# telemetry-daughter.net
KiCad netlist of a schematic drawn in EAGLE
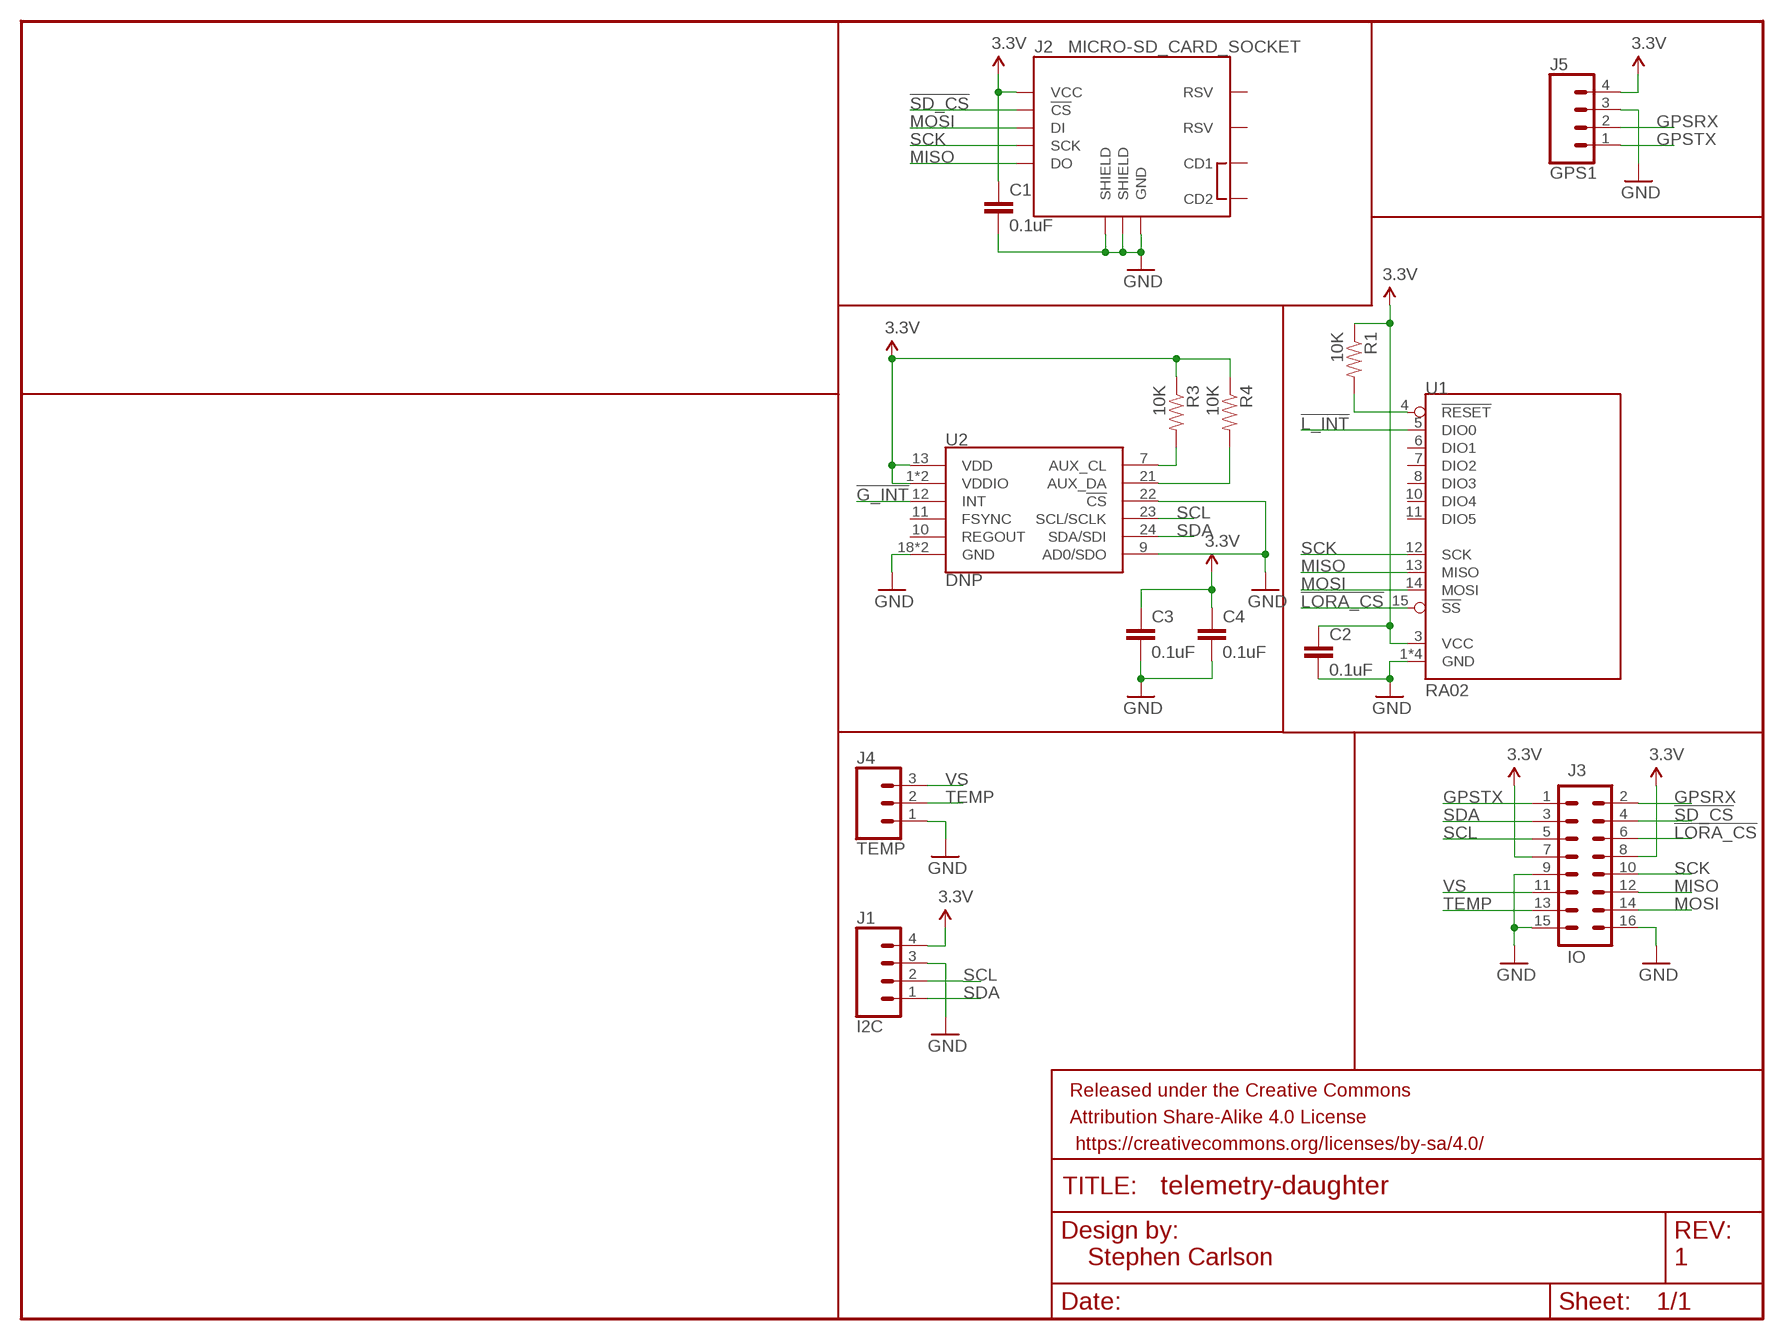
[diagram p0: schematic, sheet 1]

(export (version "E")
  (design (tool "Eeschema 10.0.6"))
  (components
    (comp (ref "C1")
      (value "0.1uF")
      (footprint "eagle-import:0603")
      (libsource (lib "eagle-import") (part "0.1UF-0603-25V-(+80/-20%)"))
    )
    (comp (ref "C2")
      (value "0.1uF")
      (footprint "eagle-import:0603")
      (libsource (lib "eagle-import") (part "0.1UF-0603-25V-(+80/-20%)"))
    )
    (comp (ref "C3")
      (value "0.1uF")
      (footprint "eagle-import:0603")
      (libsource (lib "eagle-import") (part "0.1UF-0603-25V-(+80/-20%)"))
    )
    (comp (ref "C4")
      (value "0.1uF")
      (footprint "eagle-import:0603")
      (libsource (lib "eagle-import") (part "0.1UF-0603-25V-(+80/-20%)"))
    )
    (comp (ref "FRAME1")
      (value "FRAME-LETTERNO_PACKAGE")
      (footprint "eagle-import:DUMMY")
      (fields (field (name "DESIGNER") "Nobody"))
      (libsource (lib "eagle-import") (part "FRAME-LETTERNO_PACKAGE"))
    )
    (comp (ref "J1")
      (value "I2C")
      (footprint "eagle-import:JST-4-PTH")
      (libsource (lib "eagle-import") (part "CONN_04JST-PTH"))
    )
    (comp (ref "J2")
      (value "MICRO-SD_CARD_SOCKET")
      (footprint "eagle-import:MICRO-SD-SOCKET")
      (libsource (lib "eagle-import") (part "MICRO-SD_CARD_SOCKET"))
    )
    (comp (ref "J3")
      (value "IO")
      (footprint "eagle-import:2X8")
      (libsource (lib "eagle-import") (part "M08X2"))
    )
    (comp (ref "J4")
      (value "TEMP")
      (footprint "eagle-import:JST-3-PTH")
      (libsource (lib "eagle-import") (part "CONN_03JST-PTH"))
    )
    (comp (ref "J5")
      (value "GPS1")
      (footprint "eagle-import:JST-4-PTH")
      (libsource (lib "eagle-import") (part "CONN_04JST-PTH"))
    )
    (comp (ref "R1")
      (value "10K")
      (footprint "eagle-import:0805")
      (libsource (lib "eagle-import") (part "RESISTOR0805-RES"))
    )
    (comp (ref "R3")
      (value "10K")
      (footprint "eagle-import:0805")
      (libsource (lib "eagle-import") (part "RESISTOR0805-RES"))
    )
    (comp (ref "R4")
      (value "10K")
      (footprint "eagle-import:0805")
      (libsource (lib "eagle-import") (part "RESISTOR0805-RES"))
    )
    (comp (ref "U1")
      (value "RA02")
      (footprint "eagle-import:RA02")
      (libsource (lib "eagle-import") (part "RA02"))
    )
    (comp (ref "U2")
      (value "DNP")
      (footprint "eagle-import:QFN24-3X3")
      (libsource (lib "eagle-import") (part "MPU-9250"))
    )
  )
  (nets
    (net (code "1") (name "/GPSRX") (class "Default")
      (node (ref "J3") (pin "2") (pinfunction "2_2") (pintype "passive"))
      (node (ref "J5") (pin "2") (pinfunction "2_2") (pintype "passive"))
    )
    (net (code "2") (name "/GPSTX") (class "Default")
      (node (ref "J3") (pin "1") (pinfunction "1_1") (pintype "passive"))
      (node (ref "J5") (pin "1") (pinfunction "1_1") (pintype "passive"))
    )
    (net (code "3") (name "/MISO") (class "Default")
      (node (ref "J2") (pin "DO") (pinfunction "DO_DO") (pintype "bidirectional"))
      (node (ref "J3") (pin "12") (pinfunction "12_12") (pintype "passive"))
      (node (ref "U1") (pin "13") (pinfunction "MISO_13") (pintype "output"))
    )
    (net (code "4") (name "/MOSI") (class "Default")
      (node (ref "J2") (pin "DI") (pinfunction "DI_DI") (pintype "bidirectional"))
      (node (ref "J3") (pin "14") (pinfunction "14_14") (pintype "passive"))
      (node (ref "U1") (pin "14") (pinfunction "MOSI_14") (pintype "input"))
    )
    (net (code "5") (name "/SCK") (class "Default")
      (node (ref "J2") (pin "SCLK") (pinfunction "SCK_SCLK") (pintype "bidirectional"))
      (node (ref "J3") (pin "10") (pinfunction "10_10") (pintype "passive"))
      (node (ref "U1") (pin "12") (pinfunction "SCK_12") (pintype "input"))
    )
    (net (code "6") (name "/SCL") (class "Default")
      (node (ref "J1") (pin "2") (pinfunction "2_2") (pintype "passive"))
      (node (ref "J3") (pin "5") (pinfunction "5_5") (pintype "passive"))
      (node (ref "U2") (pin "23") (pinfunction "SCL/SCLK_23") (pintype "bidirectional"))
    )
    (net (code "7") (name "/SDA") (class "Default")
      (node (ref "J1") (pin "1") (pinfunction "1_1") (pintype "passive"))
      (node (ref "J3") (pin "3") (pinfunction "3_3") (pintype "passive"))
      (node (ref "U2") (pin "24") (pinfunction "SDA/SDI_24") (pintype "bidirectional"))
    )
    (net (code "8") (name "/TEMP") (class "Default")
      (node (ref "J3") (pin "13") (pinfunction "13_13") (pintype "passive"))
      (node (ref "J4") (pin "2") (pinfunction "2_2") (pintype "passive"))
    )
    (net (code "9") (name "/VS") (class "Default")
      (node (ref "J3") (pin "11") (pinfunction "11_11") (pintype "passive"))
      (node (ref "J4") (pin "3") (pinfunction "3_3") (pintype "passive"))
    )
    (net (code "10") (name "/~{G_INT}") (class "Default")
      (node (ref "U2") (pin "12") (pinfunction "INT_12") (pintype "bidirectional"))
    )
    (net (code "11") (name "/~{LORA_CS}") (class "Default")
      (node (ref "J3") (pin "6") (pinfunction "6_6") (pintype "passive"))
      (node (ref "U1") (pin "15") (pinfunction "~{SS}_15") (pintype "input"))
    )
    (net (code "12") (name "/~{L_INT}") (class "Default")
      (node (ref "U1") (pin "5") (pinfunction "DIO0_5") (pintype "bidirectional"))
    )
    (net (code "13") (name "/~{SD_CS}") (class "Default")
      (node (ref "J2") (pin "CS") (pinfunction "~{CS}_CS") (pintype "bidirectional"))
      (node (ref "J3") (pin "4") (pinfunction "4_4") (pintype "passive"))
    )
    (net (code "14") (name "3.3V") (class "Default")
      (node (ref "C1") (pin "1") (pinfunction "1_1") (pintype "passive"))
      (node (ref "C2") (pin "1") (pinfunction "1_1") (pintype "passive"))
      (node (ref "C3") (pin "1") (pinfunction "1_1") (pintype "passive"))
      (node (ref "C4") (pin "1") (pinfunction "1_1") (pintype "passive"))
      (node (ref "J1") (pin "4") (pinfunction "4_4") (pintype "passive"))
      (node (ref "J2") (pin "VCC") (pinfunction "VCC_VCC") (pintype "bidirectional"))
      (node (ref "J3") (pin "7") (pinfunction "7_7") (pintype "passive"))
      (node (ref "J3") (pin "8") (pinfunction "8_8") (pintype "passive"))
      (node (ref "J5") (pin "4") (pinfunction "4_4") (pintype "passive"))
      (node (ref "R1") (pin "1") (pinfunction "1_1") (pintype "passive"))
      (node (ref "R3") (pin "1") (pinfunction "1_1") (pintype "passive"))
      (node (ref "R4") (pin "1") (pinfunction "1_1") (pintype "passive"))
      (node (ref "U1") (pin "3") (pinfunction "VCC_3") (pintype "power_in"))
      (node (ref "U2") (pin "1") (pinfunction "VDDIO_1") (pintype "bidirectional"))
      (node (ref "U2") (pin "13") (pinfunction "VDD_13") (pintype "bidirectional"))
      (node (ref "U2") (pin "8") (pinfunction "VDDIO_8") (pintype "bidirectional"))
    )
    (net (code "15") (name "GND") (class "Default")
      (node (ref "C1") (pin "2") (pinfunction "2_2") (pintype "passive"))
      (node (ref "C2") (pin "2") (pinfunction "2_2") (pintype "passive"))
      (node (ref "C3") (pin "2") (pinfunction "2_2") (pintype "passive"))
      (node (ref "C4") (pin "2") (pinfunction "2_2") (pintype "passive"))
      (node (ref "J1") (pin "3") (pinfunction "3_3") (pintype "passive"))
      (node (ref "J2") (pin "GND") (pinfunction "GND_GND") (pintype "bidirectional"))
      (node (ref "J2") (pin "GND1") (pinfunction "SHIELD_GND1") (pintype "bidirectional"))
      (node (ref "J2") (pin "GND3") (pinfunction "SHIELD_GND3") (pintype "bidirectional"))
      (node (ref "J3") (pin "15") (pinfunction "15_15") (pintype "passive"))
      (node (ref "J3") (pin "16") (pinfunction "16_16") (pintype "passive"))
      (node (ref "J3") (pin "9") (pinfunction "9_9") (pintype "passive"))
      (node (ref "J4") (pin "1") (pinfunction "1_1") (pintype "passive"))
      (node (ref "J5") (pin "3") (pinfunction "3_3") (pintype "passive"))
      (node (ref "U1") (pin "1") (pinfunction "GND_1") (pintype "power_in"))
      (node (ref "U1") (pin "16") (pinfunction "GND_16") (pintype "power_in"))
      (node (ref "U1") (pin "2") (pinfunction "GND_2") (pintype "power_in"))
      (node (ref "U1") (pin "9") (pinfunction "GND_9") (pintype "power_in"))
      (node (ref "U2") (pin "18") (pinfunction "GND_18") (pintype "bidirectional"))
      (node (ref "U2") (pin "20") (pinfunction "GND_20") (pintype "bidirectional"))
      (node (ref "U2") (pin "22") (pinfunction "~{CS}_22") (pintype "bidirectional"))
      (node (ref "U2") (pin "9") (pinfunction "AD0/SDO_9") (pintype "bidirectional"))
    )
    (net (code "16") (name "Net-(U1-~{RESET})") (class "Default")
      (node (ref "R1") (pin "2") (pinfunction "2_2") (pintype "passive"))
      (node (ref "U1") (pin "4") (pinfunction "~{RESET}_4") (pintype "input"))
    )
    (net (code "17") (name "Net-(U2-AUX_CL)") (class "Default")
      (node (ref "R3") (pin "2") (pinfunction "2_2") (pintype "passive"))
      (node (ref "U2") (pin "7") (pinfunction "AUX_CL_7") (pintype "bidirectional"))
    )
    (net (code "18") (name "Net-(U2-AUX_DA)") (class "Default")
      (node (ref "R4") (pin "2") (pinfunction "2_2") (pintype "passive"))
      (node (ref "U2") (pin "21") (pinfunction "AUX_DA_21") (pintype "bidirectional"))
    )
    (net (code "19") (name "unconnected-(J2-PadCD1)") (class "Default")
      (node (ref "J2") (pin "CD1") (pinfunction "CD1_CD1") (pintype "bidirectional"))
    )
    (net (code "20") (name "unconnected-(J2-PadCD2)") (class "Default")
      (node (ref "J2") (pin "CD2") (pinfunction "CD2_CD2") (pintype "bidirectional"))
    )
    (net (code "21") (name "unconnected-(J2-RSV-PadRSV1)") (class "Default")
      (node (ref "J2") (pin "RSV1") (pinfunction "RSV_RSV1") (pintype "bidirectional"))
    )
    (net (code "22") (name "unconnected-(J2-RSV-PadRSV2)") (class "Default")
      (node (ref "J2") (pin "RSV2") (pinfunction "RSV_RSV2") (pintype "bidirectional"))
    )
    (net (code "23") (name "unconnected-(U1-DIO1-Pad6)") (class "Default")
      (node (ref "U1") (pin "6") (pinfunction "DIO1_6") (pintype "bidirectional"))
    )
    (net (code "24") (name "unconnected-(U1-DIO2-Pad7)") (class "Default")
      (node (ref "U1") (pin "7") (pinfunction "DIO2_7") (pintype "bidirectional"))
    )
    (net (code "25") (name "unconnected-(U1-DIO3-Pad8)") (class "Default")
      (node (ref "U1") (pin "8") (pinfunction "DIO3_8") (pintype "bidirectional"))
    )
    (net (code "26") (name "unconnected-(U1-DIO4-Pad10)") (class "Default")
      (node (ref "U1") (pin "10") (pinfunction "DIO4_10") (pintype "bidirectional"))
    )
    (net (code "27") (name "unconnected-(U1-DIO5-Pad11)") (class "Default")
      (node (ref "U1") (pin "11") (pinfunction "DIO5_11") (pintype "bidirectional"))
    )
    (net (code "28") (name "unconnected-(U2-FSYNC-Pad11)") (class "Default")
      (node (ref "U2") (pin "11") (pinfunction "FSYNC_11") (pintype "bidirectional"))
    )
    (net (code "29") (name "unconnected-(U2-REGOUT-Pad10)") (class "Default")
      (node (ref "U2") (pin "10") (pinfunction "REGOUT_10") (pintype "bidirectional"))
    )
  )
)
